# Sheet1.net
KiCad netlist of a schematic drawn in Altium Designer
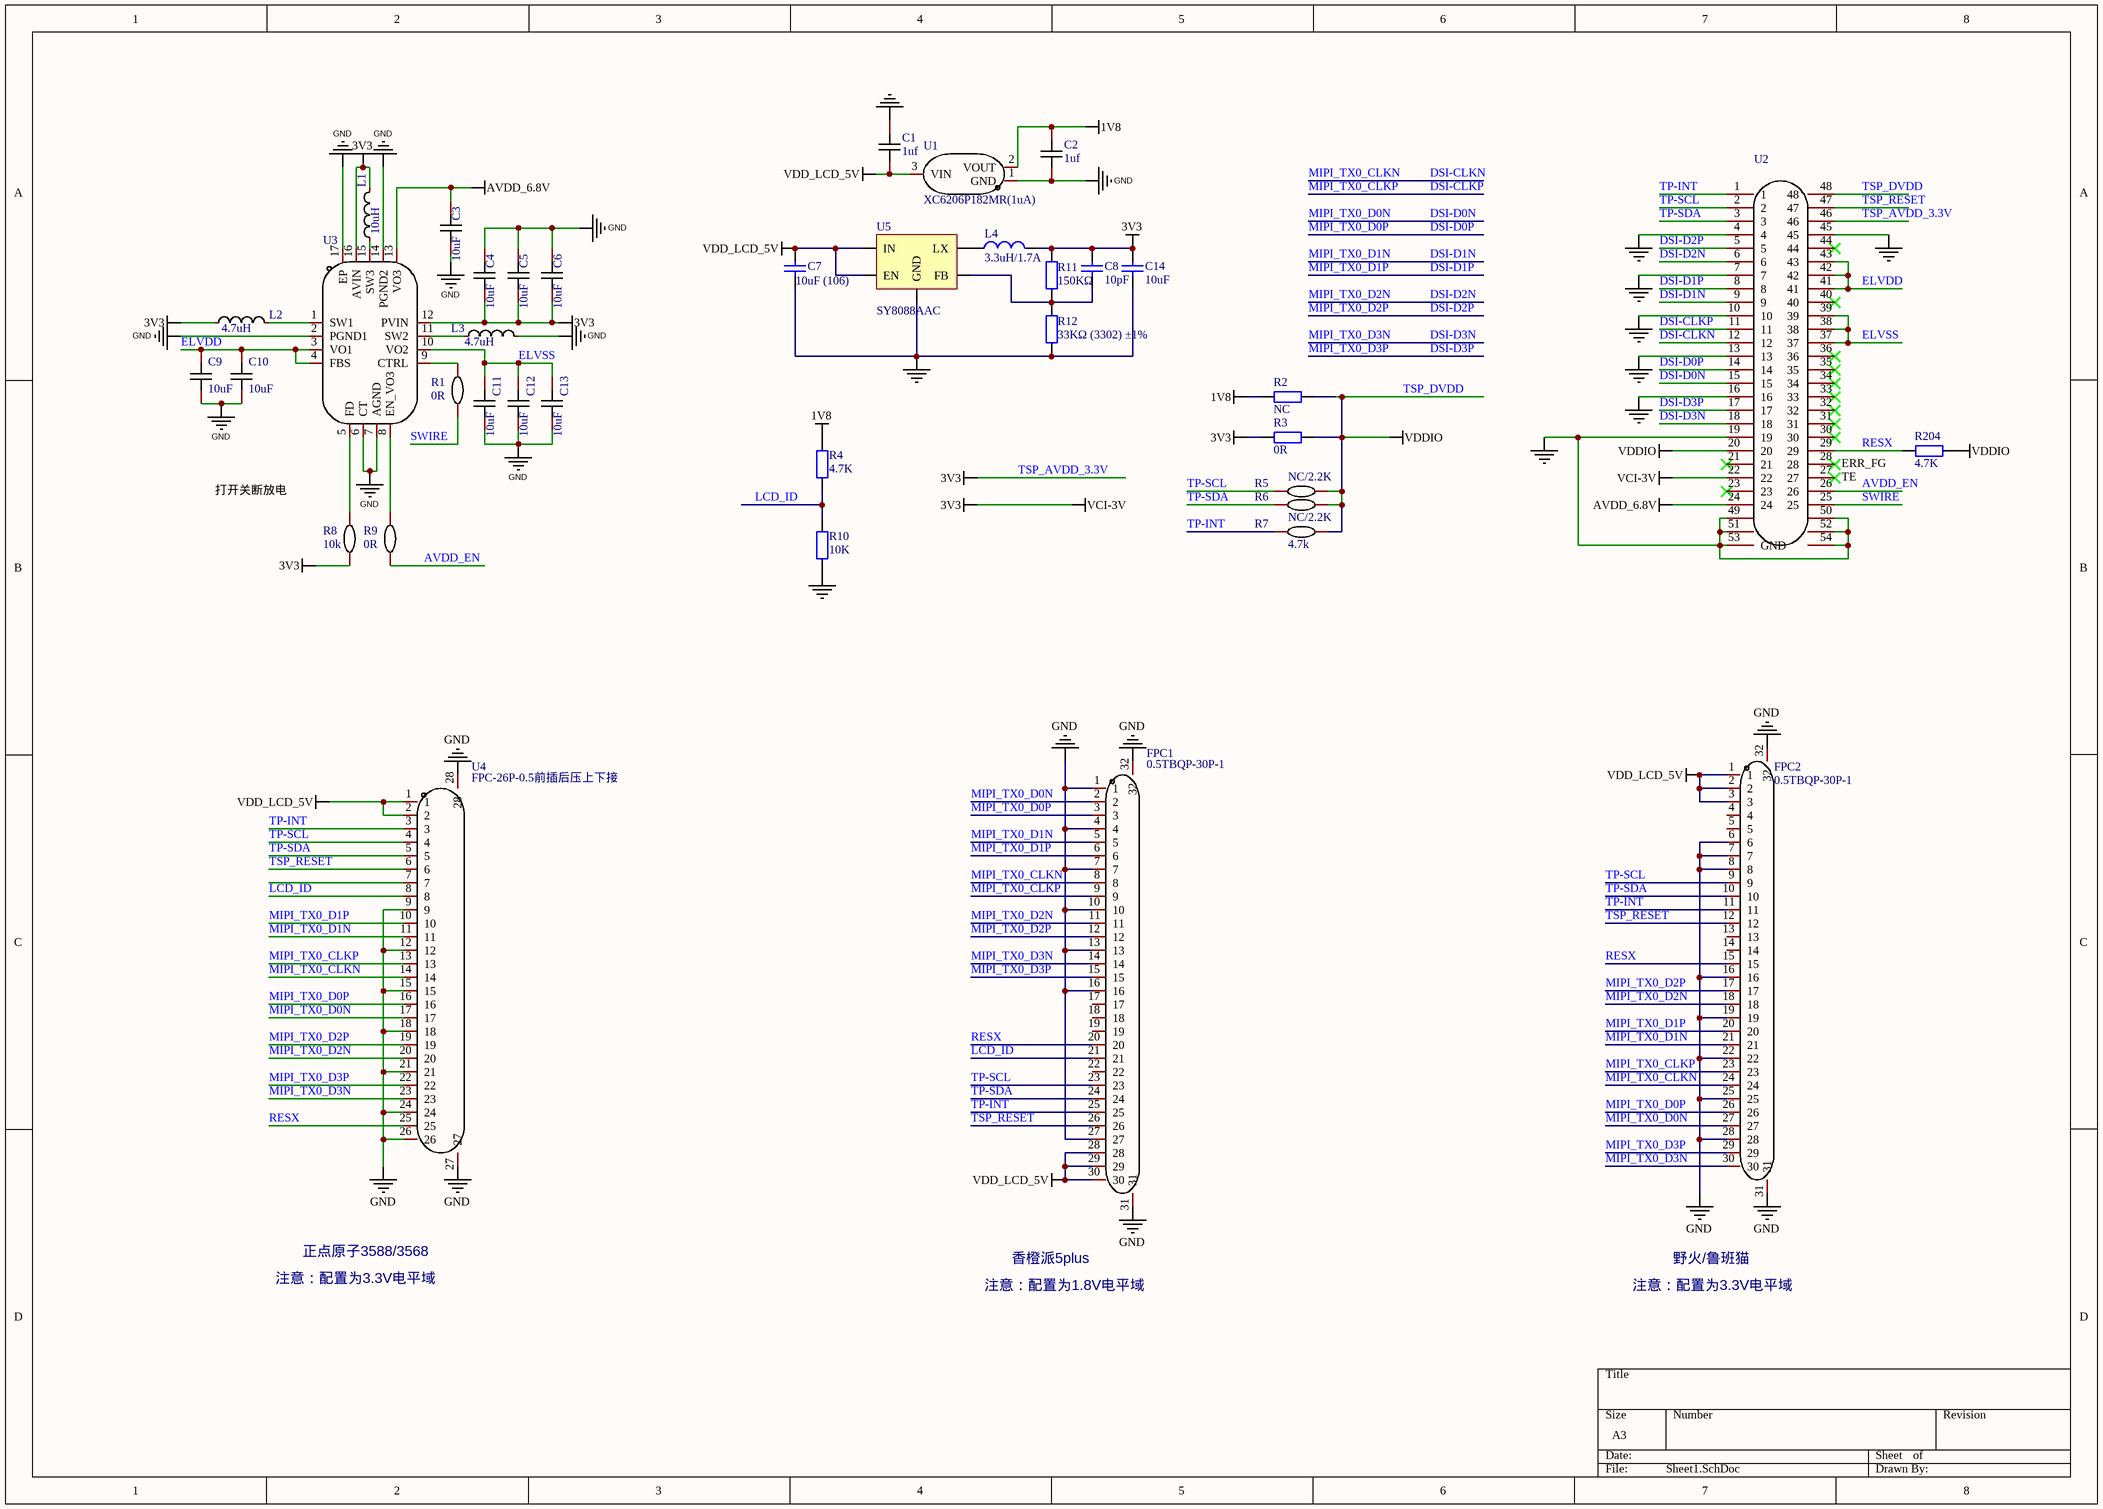
[diagram p0: Sheet1.SchDoc]

(export (version "E")
  (design (tool "Eeschema 10.0.6"))
  (components
    (comp (ref "C1")
      (value "1uf")
      (footprint "C0603")
      (fields (field (name "NAME") "1uf"))
      (libsource (lib "altium-import") (part "root_3_CAP_0603_"))
    )
    (comp (ref "C2")
      (value "1uf")
      (footprint "C0603")
      (fields (field (name "NAME") "1uf"))
      (libsource (lib "altium-import") (part "root_3_CAP_0603_"))
    )
    (comp (ref "C3")
      (value "10uF")
      (footprint "C0603")
      (fields (field (name "NAME") "10uF"))
      (libsource (lib "altium-import") (part "root_1_CAP_0603_"))
    )
    (comp (ref "C4")
      (value "10uF")
      (footprint "C0603")
      (fields (field (name "NAME") "10uF"))
      (libsource (lib "altium-import") (part "root_1_CAP_0603_"))
    )
    (comp (ref "C5")
      (value "10uF")
      (footprint "C0603")
      (fields (field (name "NAME") "10uF"))
      (libsource (lib "altium-import") (part "root_1_CAP_0603_"))
    )
    (comp (ref "C6")
      (value "10uF")
      (footprint "C0603")
      (fields (field (name "NAME") "10uF"))
      (libsource (lib "altium-import") (part "root_1_CAP_0603_"))
    )
    (comp (ref "C7")
      (value "10uF (106)")
      (footprint "C 0603")
      (description "贴片电容")
      (libsource (lib "Miscellaneous Devices LC") (part "0603 10uF (106) 10% 10V"))
    )
    (comp (ref "C8")
      (value "10pF")
      (footprint "C 0603")
      (description "贴片电容")
      (libsource (lib "Miscellaneous Devices LC") (part "0402 10pF (100) 5% 50V"))
    )
    (comp (ref "C9")
      (value "10uF")
      (footprint "C0603")
      (fields (field (name "NAME") "10uF"))
      (libsource (lib "altium-import") (part "root_1_CAP_0603_"))
    )
    (comp (ref "C10")
      (value "10uF")
      (footprint "C0603")
      (fields (field (name "NAME") "10uF"))
      (libsource (lib "altium-import") (part "root_1_CAP_0603_"))
    )
    (comp (ref "C11")
      (value "10uF")
      (footprint "C0603")
      (fields (field (name "NAME") "10uF"))
      (libsource (lib "altium-import") (part "root_1_CAP_0603_"))
    )
    (comp (ref "C12")
      (value "10uF")
      (footprint "C0603")
      (fields (field (name "NAME") "10uF"))
      (libsource (lib "altium-import") (part "root_1_CAP_0603_"))
    )
    (comp (ref "C13")
      (value "10uF")
      (footprint "C0603")
      (fields (field (name "NAME") "10uF"))
      (libsource (lib "altium-import") (part "root_1_CAP_0603_"))
    )
    (comp (ref "C14")
      (value "10uF")
      (footprint "C 0603")
      (description "贴片电容")
      (libsource (lib "Miscellaneous Devices LC") (part "0603 10uF (106) 10% 10V"))
    )
    (comp (ref "FPC1")
      (value "0.5TBQP-30P-1")
      (footprint "FPC-SMD_30P-P0.50_0.5TBQS-30P-1")
      (fields (field (name "NAME") "0.5TBQP-30P-1"))
      (libsource (lib "altium-import") (part "root_0_0.5TBQP-30P-1_"))
    )
    (comp (ref "FPC2")
      (value "0.5TBQP-30P-1")
      (footprint "FPC-SMD_30P-P0.50_0.5TBQS-30P-1")
      (fields (field (name "NAME") "0.5TBQP-30P-1"))
      (libsource (lib "altium-import") (part "root_0_0.5TBQP-30P-1_"))
    )
    (comp (ref "L1")
      (value "10uH")
      (footprint "IND-SMD_L2.7-W2.0")
      (description "电感值:2.2uH;精度:±20%;额定电流:1.3A;")
      (fields
        (field (name "NAME") "10uH")
        (field (name "MANUFACTURER") "gotrend(高创科技)")
        (field (name "MANUFACTURER PART") "GNR2512PA-2R2M")
      )
      (libsource (lib "altium-import") (part "root_1_GNR2512PA-2R2M_"))
    )
    (comp (ref "L2")
      (value "4.7uH")
      (footprint "IND-SMD_L2.7-W2.0")
      (description "电感值:2.2uH;精度:±20%;额定电流:1.3A;")
      (fields
        (field (name "NAME") "4.7uH")
        (field (name "MANUFACTURER") "gotrend(高创科技)")
        (field (name "MANUFACTURER PART") "GNR2512PA-2R2M")
      )
      (libsource (lib "altium-import") (part "root_0_GNR2512PA-2R2M_"))
    )
    (comp (ref "L3")
      (value "4.7uH")
      (footprint "IND-SMD_L2.7-W2.0")
      (description "电感值:2.2uH;精度:±20%;额定电流:1.3A;")
      (fields
        (field (name "NAME") "4.7uH")
        (field (name "MANUFACTURER") "gotrend(高创科技)")
        (field (name "MANUFACTURER PART") "GNR2512PA-2R2M")
      )
      (libsource (lib "altium-import") (part "root_0_GNR2512PA-2R2M_"))
    )
    (comp (ref "L4")
      (value "3.3uH/1.7A")
      (footprint "1008")
      (description "电感")
      (libsource (lib "YZL_Library") (part "Inductor"))
    )
    (comp (ref "R1")
      (value "0R")
      (footprint "R0603")
      (libsource (lib "altium-import") (part "root_1_Res_0603_"))
    )
    (comp (ref "R2")
      (value "NC")
      (footprint "R 0603")
      (description "贴片电阻")
      (fields (field (name "版权归属") "源创客"))
      (libsource (lib "电阻-电容-电感") (part "R"))
    )
    (comp (ref "R3")
      (value "0R")
      (footprint "R 0603")
      (description "贴片电阻")
      (fields (field (name "版权归属") "源创客"))
      (libsource (lib "电阻-电容-电感") (part "R"))
    )
    (comp (ref "R4")
      (value "4.7K")
      (footprint "R 0603")
      (description "贴片电阻")
      (fields (field (name "版权归属") "源创客"))
      (libsource (lib "电阻-电容-电感") (part "R"))
    )
    (comp (ref "R5")
      (value "NC/2.2K")
      (footprint "R0603")
      (libsource (lib "altium-import") (part "root_0_Res_0603_"))
    )
    (comp (ref "R6")
      (value "NC/2.2K")
      (footprint "R0603")
      (libsource (lib "altium-import") (part "root_0_Res_0603_"))
    )
    (comp (ref "R7")
      (value "4.7k")
      (footprint "R0603")
      (libsource (lib "altium-import") (part "root_0_Res_0603_"))
    )
    (comp (ref "R8")
      (value "10k")
      (footprint "R0603")
      (libsource (lib "altium-import") (part "root_1_Res_0603_"))
    )
    (comp (ref "R9")
      (value "0R")
      (footprint "R0603")
      (libsource (lib "altium-import") (part "root_1_Res_0603_"))
    )
    (comp (ref "R10")
      (value "10K")
      (footprint "R 0603")
      (description "贴片电阻")
      (fields (field (name "版权归属") "源创客"))
      (libsource (lib "电阻-电容-电感") (part "R"))
    )
    (comp (ref "R11")
      (value "150KΩ")
      (footprint "R 0603")
      (description "贴片电阻")
      (libsource (lib "Miscellaneous Devices LC") (part "0402 150KΩ (1503) 1%"))
    )
    (comp (ref "R12")
      (value "33KΩ (3302) ±1%")
      (footprint "R 0603")
      (description "贴片电阻")
      (libsource (lib "Miscellaneous Devices LC") (part "0402 33KΩ (3302) 1%"))
    )
    (comp (ref "R204")
      (value "4.7K")
      (footprint "R 0603")
      (description "贴片电阻")
      (fields (field (name "版权归属") "源创客"))
      (libsource (lib "电阻-电容-电感") (part "R"))
    )
    (comp (ref "U1")
      (value "XC6206P182MR(1uA)")
      (footprint "SOT-23-3_L2.9-W1.6-P1.90-LS2.8-BR")
      (description "输出类型:-;")
      (fields (field (name "NAME") "XC6206P182MR(1uA)") (field (name "MANUFACTURER") "TECH PUBLIC(台舟)"))
      (libsource (lib "altium-import") (part "root_2_XC6206P182MR(1uA)_"))
    )
    (comp (ref "U2")
      (value "24-5857-048-201-829+")
      (footprint "BTB-24-5857-048")
      (libsource (lib "altium-import") (part "root_0_24-5857-048-201-829+_"))
    )
    (comp (ref "U3")
      (value "SGM3836AYTQ16G/TR")
      (footprint "TQFN-16_L3.0-W3.0-P0.50-BL-EP1.7")
      (fields (field (name "MANUFACTURER") "SGMICRO(圣邦微)"))
      (libsource (lib "altium-import") (part "root_0_SGM3836AYTQ16G/TR_"))
    )
    (comp (ref "U4")
      (value "FPC-26P-0.5前插后压上下接")
      (footprint "FPC-SMD_26P-P0.50_C9900017209")
      (fields (field (name "NAME") "FPC-26P-0.5前插后压上下接"))
      (libsource (lib "altium-import") (part "root_0_FPC-26P-0.5前插后压上下接_"))
    )
    (comp (ref "U5")
      (value "SY8088AAC")
      (footprint "SOT23-5N")
      (description "1.5M 1A DCDC")
      (libsource (lib "YZL_Library") (part "SY8088AAC"))
    )
  )
  (nets
    (net (code "1") (name "/AVDD_EN") (class "Default")
      (node (ref "R9") (pin "1") (pinfunction "1_1") (pintype "passive"))
      (node (ref "U2") (pin "26") (pinfunction "26_26") (pintype "passive"))
    )
    (net (code "2") (name "/DSI-CLKN") (class "Default")
      (node (ref "FPC1") (pin "8") (pinfunction "8_8") (pintype "passive"))
      (node (ref "FPC2") (pin "24") (pinfunction "24_24") (pintype "passive"))
      (node (ref "U2") (pin "12") (pinfunction "12_12") (pintype "passive"))
      (node (ref "U4") (pin "14") (pinfunction "14_14") (pintype "passive"))
    )
    (net (code "3") (name "/DSI-CLKP") (class "Default")
      (node (ref "FPC1") (pin "9") (pinfunction "9_9") (pintype "passive"))
      (node (ref "FPC2") (pin "23") (pinfunction "23_23") (pintype "passive"))
      (node (ref "U2") (pin "11") (pinfunction "11_11") (pintype "passive"))
      (node (ref "U4") (pin "13") (pinfunction "13_13") (pintype "passive"))
    )
    (net (code "4") (name "/DSI-D0N") (class "Default")
      (node (ref "FPC1") (pin "2") (pinfunction "2_2") (pintype "passive"))
      (node (ref "FPC2") (pin "27") (pinfunction "27_27") (pintype "passive"))
      (node (ref "U2") (pin "15") (pinfunction "15_15") (pintype "passive"))
      (node (ref "U4") (pin "17") (pinfunction "17_17") (pintype "passive"))
    )
    (net (code "5") (name "/DSI-D0P") (class "Default")
      (node (ref "FPC1") (pin "3") (pinfunction "3_3") (pintype "passive"))
      (node (ref "FPC2") (pin "26") (pinfunction "26_26") (pintype "passive"))
      (node (ref "U2") (pin "14") (pinfunction "14_14") (pintype "passive"))
      (node (ref "U4") (pin "16") (pinfunction "16_16") (pintype "passive"))
    )
    (net (code "6") (name "/DSI-D1N") (class "Default")
      (node (ref "FPC1") (pin "5") (pinfunction "5_5") (pintype "passive"))
      (node (ref "FPC2") (pin "21") (pinfunction "21_21") (pintype "passive"))
      (node (ref "U2") (pin "9") (pinfunction "9_9") (pintype "passive"))
      (node (ref "U4") (pin "11") (pinfunction "11_11") (pintype "passive"))
    )
    (net (code "7") (name "/DSI-D1P") (class "Default")
      (node (ref "FPC1") (pin "6") (pinfunction "6_6") (pintype "passive"))
      (node (ref "FPC2") (pin "20") (pinfunction "20_20") (pintype "passive"))
      (node (ref "U2") (pin "8") (pinfunction "8_8") (pintype "passive"))
      (node (ref "U4") (pin "10") (pinfunction "10_10") (pintype "passive"))
    )
    (net (code "8") (name "/DSI-D2N") (class "Default")
      (node (ref "FPC1") (pin "11") (pinfunction "11_11") (pintype "passive"))
      (node (ref "FPC2") (pin "18") (pinfunction "18_18") (pintype "passive"))
      (node (ref "U2") (pin "6") (pinfunction "6_6") (pintype "passive"))
      (node (ref "U4") (pin "20") (pinfunction "20_20") (pintype "passive"))
    )
    (net (code "9") (name "/DSI-D2P") (class "Default")
      (node (ref "FPC1") (pin "12") (pinfunction "12_12") (pintype "passive"))
      (node (ref "FPC2") (pin "17") (pinfunction "17_17") (pintype "passive"))
      (node (ref "U2") (pin "5") (pinfunction "5_5") (pintype "passive"))
      (node (ref "U4") (pin "19") (pinfunction "19_19") (pintype "passive"))
    )
    (net (code "10") (name "/DSI-D3N") (class "Default")
      (node (ref "FPC1") (pin "14") (pinfunction "14_14") (pintype "passive"))
      (node (ref "FPC2") (pin "30") (pinfunction "30_30") (pintype "passive"))
      (node (ref "U2") (pin "18") (pinfunction "18_18") (pintype "passive"))
      (node (ref "U4") (pin "23") (pinfunction "23_23") (pintype "passive"))
    )
    (net (code "11") (name "/DSI-D3P") (class "Default")
      (node (ref "FPC1") (pin "15") (pinfunction "15_15") (pintype "passive"))
      (node (ref "FPC2") (pin "29") (pinfunction "29_29") (pintype "passive"))
      (node (ref "U2") (pin "17") (pinfunction "17_17") (pintype "passive"))
      (node (ref "U4") (pin "22") (pinfunction "22_22") (pintype "passive"))
    )
    (net (code "12") (name "/ELVDD") (class "Default")
      (node (ref "C10") (pin "2") (pinfunction "2_2") (pintype "passive"))
      (node (ref "C9") (pin "2") (pinfunction "2_2") (pintype "passive"))
      (node (ref "U2") (pin "41") (pinfunction "41_41") (pintype "passive"))
      (node (ref "U2") (pin "42") (pinfunction "42_42") (pintype "passive"))
      (node (ref "U2") (pin "43") (pinfunction "43_43") (pintype "passive"))
      (node (ref "U3") (pin "3") (pinfunction "VO1_3") (pintype "passive"))
      (node (ref "U3") (pin "4") (pinfunction "FBS_4") (pintype "passive"))
    )
    (net (code "13") (name "/ELVSS") (class "Default")
      (node (ref "C11") (pin "2") (pinfunction "2_2") (pintype "passive"))
      (node (ref "C12") (pin "2") (pinfunction "2_2") (pintype "passive"))
      (node (ref "C13") (pin "2") (pinfunction "2_2") (pintype "passive"))
      (node (ref "U2") (pin "37") (pinfunction "37_37") (pintype "passive"))
      (node (ref "U2") (pin "38") (pinfunction "38_38") (pintype "passive"))
      (node (ref "U2") (pin "39") (pinfunction "39_39") (pintype "passive"))
      (node (ref "U3") (pin "10") (pinfunction "VO2_10") (pintype "passive"))
    )
    (net (code "14") (name "/LCD_ID") (class "Default")
      (node (ref "FPC1") (pin "21") (pinfunction "21_21") (pintype "passive"))
      (node (ref "R10") (pin "2") (pinfunction "2_2") (pintype "passive"))
      (node (ref "R4") (pin "2") (pinfunction "2_2") (pintype "passive"))
      (node (ref "U4") (pin "8") (pinfunction "8_8") (pintype "passive"))
    )
    (net (code "15") (name "/RESX") (class "Default")
      (node (ref "FPC1") (pin "20") (pinfunction "20_20") (pintype "passive"))
      (node (ref "FPC2") (pin "15") (pinfunction "15_15") (pintype "passive"))
      (node (ref "R204") (pin "1") (pinfunction "1_1") (pintype "passive"))
      (node (ref "U2") (pin "29") (pinfunction "29_29") (pintype "passive"))
      (node (ref "U4") (pin "25") (pinfunction "25_25") (pintype "passive"))
    )
    (net (code "16") (name "/SWIRE") (class "Default")
      (node (ref "R1") (pin "1") (pinfunction "1_1") (pintype "passive"))
      (node (ref "U2") (pin "25") (pinfunction "25_25") (pintype "passive"))
    )
    (net (code "17") (name "/TP-INT") (class "Default")
      (node (ref "FPC1") (pin "25") (pinfunction "25_25") (pintype "passive"))
      (node (ref "FPC2") (pin "11") (pinfunction "11_11") (pintype "passive"))
      (node (ref "R7") (pin "1") (pinfunction "1_1") (pintype "passive"))
      (node (ref "U2") (pin "1") (pinfunction "1_1") (pintype "passive"))
      (node (ref "U4") (pin "3") (pinfunction "3_3") (pintype "passive"))
    )
    (net (code "18") (name "/TP-SCL") (class "Default")
      (node (ref "FPC1") (pin "23") (pinfunction "23_23") (pintype "passive"))
      (node (ref "FPC2") (pin "9") (pinfunction "9_9") (pintype "passive"))
      (node (ref "R5") (pin "1") (pinfunction "1_1") (pintype "passive"))
      (node (ref "U2") (pin "2") (pinfunction "2_2") (pintype "passive"))
      (node (ref "U4") (pin "4") (pinfunction "4_4") (pintype "passive"))
    )
    (net (code "19") (name "/TP-SDA") (class "Default")
      (node (ref "FPC1") (pin "24") (pinfunction "24_24") (pintype "passive"))
      (node (ref "FPC2") (pin "10") (pinfunction "10_10") (pintype "passive"))
      (node (ref "R6") (pin "1") (pinfunction "1_1") (pintype "passive"))
      (node (ref "U2") (pin "3") (pinfunction "3_3") (pintype "passive"))
      (node (ref "U4") (pin "5") (pinfunction "5_5") (pintype "passive"))
    )
    (net (code "20") (name "/TSP_RESET") (class "Default")
      (node (ref "FPC1") (pin "26") (pinfunction "26_26") (pintype "passive"))
      (node (ref "FPC2") (pin "12") (pinfunction "12_12") (pintype "passive"))
      (node (ref "U2") (pin "47") (pinfunction "47_47") (pintype "passive"))
      (node (ref "U4") (pin "6") (pinfunction "6_6") (pintype "passive"))
    )
    (net (code "21") (name "1V8") (class "Default")
      (node (ref "C2") (pin "1") (pinfunction "1_1") (pintype "passive"))
      (node (ref "R2") (pin "1") (pinfunction "1_1") (pintype "passive"))
      (node (ref "R4") (pin "1") (pinfunction "1_1") (pintype "passive"))
      (node (ref "U1") (pin "2") (pinfunction "VOUT_2") (pintype "passive"))
    )
    (net (code "22") (name "3V3") (class "Default")
      (node (ref "C14") (pin "2") (pinfunction "2_2") (pintype "passive"))
      (node (ref "C4") (pin "1") (pinfunction "1_1") (pintype "passive"))
      (node (ref "C5") (pin "1") (pinfunction "1_1") (pintype "passive"))
      (node (ref "C6") (pin "1") (pinfunction "1_1") (pintype "passive"))
      (node (ref "C8") (pin "2") (pinfunction "2_2") (pintype "passive"))
      (node (ref "L1") (pin "2") (pinfunction "2_2") (pintype "passive"))
      (node (ref "L2") (pin "1") (pinfunction "1_1") (pintype "passive"))
      (node (ref "L4") (pin "2") (pinfunction "2_2") (pintype "passive"))
      (node (ref "R11") (pin "2") (pinfunction "2_2") (pintype "passive"))
      (node (ref "R3") (pin "1") (pinfunction "1_1") (pintype "passive"))
      (node (ref "R8") (pin "1") (pinfunction "1_1") (pintype "passive"))
      (node (ref "U2") (pin "22") (pinfunction "22_22") (pintype "passive"))
      (node (ref "U2") (pin "46") (pinfunction "46_46") (pintype "passive"))
      (node (ref "U3") (pin "12") (pinfunction "PVIN_12") (pintype "passive"))
      (node (ref "U3") (pin "16") (pinfunction "AVIN_16") (pintype "passive"))
    )
    (net (code "23") (name "AVDD_6.8V") (class "Default")
      (node (ref "C3") (pin "2") (pinfunction "2_2") (pintype "passive"))
      (node (ref "U2") (pin "24") (pinfunction "24_24") (pintype "passive"))
      (node (ref "U3") (pin "13") (pinfunction "VO3_13") (pintype "passive"))
    )
    (net (code "24") (name "GND") (class "Default")
      (node (ref "C1") (pin "1") (pinfunction "1_1") (pintype "passive"))
      (node (ref "C10") (pin "1") (pinfunction "1_1") (pintype "passive"))
      (node (ref "C11") (pin "1") (pinfunction "1_1") (pintype "passive"))
      (node (ref "C12") (pin "1") (pinfunction "1_1") (pintype "passive"))
      (node (ref "C13") (pin "1") (pinfunction "1_1") (pintype "passive"))
      (node (ref "C14") (pin "1") (pinfunction "1_1") (pintype "passive"))
      (node (ref "C2") (pin "2") (pinfunction "2_2") (pintype "passive"))
      (node (ref "C3") (pin "1") (pinfunction "1_1") (pintype "passive"))
      (node (ref "C4") (pin "2") (pinfunction "2_2") (pintype "passive"))
      (node (ref "C5") (pin "2") (pinfunction "2_2") (pintype "passive"))
      (node (ref "C6") (pin "2") (pinfunction "2_2") (pintype "passive"))
      (node (ref "C7") (pin "1") (pinfunction "1_1") (pintype "passive"))
      (node (ref "C9") (pin "1") (pinfunction "1_1") (pintype "passive"))
      (node (ref "FPC1") (pin "1") (pinfunction "1_1") (pintype "passive"))
      (node (ref "FPC1") (pin "10") (pinfunction "10_10") (pintype "passive"))
      (node (ref "FPC1") (pin "13") (pinfunction "13_13") (pintype "passive"))
      (node (ref "FPC1") (pin "16") (pinfunction "16_16") (pintype "passive"))
      (node (ref "FPC1") (pin "27") (pinfunction "27_27") (pintype "passive"))
      (node (ref "FPC1") (pin "31") (pinfunction "31_31") (pintype "passive"))
      (node (ref "FPC1") (pin "32") (pinfunction "32_32") (pintype "passive"))
      (node (ref "FPC1") (pin "4") (pinfunction "4_4") (pintype "passive"))
      (node (ref "FPC1") (pin "7") (pinfunction "7_7") (pintype "passive"))
      (node (ref "FPC2") (pin "16") (pinfunction "16_16") (pintype "passive"))
      (node (ref "FPC2") (pin "19") (pinfunction "19_19") (pintype "passive"))
      (node (ref "FPC2") (pin "22") (pinfunction "22_22") (pintype "passive"))
      (node (ref "FPC2") (pin "25") (pinfunction "25_25") (pintype "passive"))
      (node (ref "FPC2") (pin "28") (pinfunction "28_28") (pintype "passive"))
      (node (ref "FPC2") (pin "31") (pinfunction "31_31") (pintype "passive"))
      (node (ref "FPC2") (pin "32") (pinfunction "32_32") (pintype "passive"))
      (node (ref "FPC2") (pin "6") (pinfunction "6_6") (pintype "passive"))
      (node (ref "FPC2") (pin "7") (pinfunction "7_7") (pintype "passive"))
      (node (ref "FPC2") (pin "8") (pinfunction "8_8") (pintype "passive"))
      (node (ref "L3") (pin "2") (pinfunction "2_2") (pintype "passive"))
      (node (ref "R10") (pin "1") (pinfunction "1_1") (pintype "passive"))
      (node (ref "R12") (pin "1") (pinfunction "1_1") (pintype "passive"))
      (node (ref "U1") (pin "1") (pinfunction "GND_1") (pintype "passive"))
      (node (ref "U2") (pin "10") (pinfunction "10_10") (pintype "passive"))
      (node (ref "U2") (pin "13") (pinfunction "13_13") (pintype "passive"))
      (node (ref "U2") (pin "16") (pinfunction "16_16") (pintype "passive"))
      (node (ref "U2") (pin "19") (pinfunction "19_19") (pintype "passive"))
      (node (ref "U2") (pin "4") (pinfunction "4_4") (pintype "passive"))
      (node (ref "U2") (pin "45") (pinfunction "45_45") (pintype "passive"))
      (node (ref "U2") (pin "49") (pinfunction "48_49") (pintype "passive"))
      (node (ref "U2") (pin "50") (pinfunction "48_50") (pintype "passive"))
      (node (ref "U2") (pin "51") (pinfunction "48_51") (pintype "passive"))
      (node (ref "U2") (pin "52") (pinfunction "48_52") (pintype "passive"))
      (node (ref "U2") (pin "53") (pinfunction "GND_53") (pintype "passive"))
      (node (ref "U2") (pin "54") (pinfunction "48_54") (pintype "passive"))
      (node (ref "U2") (pin "7") (pinfunction "7_7") (pintype "passive"))
      (node (ref "U3") (pin "14") (pinfunction "PGND2_14") (pintype "passive"))
      (node (ref "U3") (pin "17") (pinfunction "EP_17") (pintype "passive"))
      (node (ref "U3") (pin "2") (pinfunction "PGND1_2") (pintype "passive"))
      (node (ref "U3") (pin "6") (pinfunction "CT_6") (pintype "passive"))
      (node (ref "U3") (pin "7") (pinfunction "AGND_7") (pintype "passive"))
      (node (ref "U4") (pin "12") (pinfunction "12_12") (pintype "passive"))
      (node (ref "U4") (pin "15") (pinfunction "15_15") (pintype "passive"))
      (node (ref "U4") (pin "18") (pinfunction "18_18") (pintype "passive"))
      (node (ref "U4") (pin "21") (pinfunction "21_21") (pintype "passive"))
      (node (ref "U4") (pin "24") (pinfunction "24_24") (pintype "passive"))
      (node (ref "U4") (pin "26") (pinfunction "26_26") (pintype "passive"))
      (node (ref "U4") (pin "27") (pinfunction "27_27") (pintype "passive"))
      (node (ref "U4") (pin "28") (pinfunction "28_28") (pintype "passive"))
      (node (ref "U4") (pin "9") (pinfunction "9_9") (pintype "passive"))
      (node (ref "U5") (pin "2") (pinfunction "GND_2") (pintype "passive"))
    )
    (net (code "25") (name "Net-(U3-CTRL)") (class "Default")
      (node (ref "R1") (pin "2") (pinfunction "2_2") (pintype "passive"))
      (node (ref "U3") (pin "9") (pinfunction "CTRL_9") (pintype "passive"))
    )
    (net (code "26") (name "Net-(U3-EN_VO3)") (class "Default")
      (node (ref "R9") (pin "2") (pinfunction "2_2") (pintype "passive"))
      (node (ref "U3") (pin "8") (pinfunction "EN_VO3_8") (pintype "passive"))
    )
    (net (code "27") (name "Net-(U3-FD)") (class "Default")
      (node (ref "R8") (pin "2") (pinfunction "2_2") (pintype "passive"))
      (node (ref "U3") (pin "5") (pinfunction "FD_5") (pintype "passive"))
    )
    (net (code "28") (name "Net-(U3-SW1)") (class "Default")
      (node (ref "L2") (pin "2") (pinfunction "2_2") (pintype "passive"))
      (node (ref "U3") (pin "1") (pinfunction "SW1_1") (pintype "passive"))
    )
    (net (code "29") (name "Net-(U3-SW2)") (class "Default")
      (node (ref "L3") (pin "1") (pinfunction "1_1") (pintype "passive"))
      (node (ref "U3") (pin "11") (pinfunction "SW2_11") (pintype "passive"))
    )
    (net (code "30") (name "Net-(U3-SW3)") (class "Default")
      (node (ref "L1") (pin "1") (pinfunction "1_1") (pintype "passive"))
      (node (ref "U3") (pin "15") (pinfunction "SW3_15") (pintype "passive"))
    )
    (net (code "31") (name "Net-(U5-FB)") (class "Default")
      (node (ref "C8") (pin "1") (pinfunction "1_1") (pintype "passive"))
      (node (ref "R11") (pin "1") (pinfunction "1_1") (pintype "passive"))
      (node (ref "R12") (pin "2") (pinfunction "2_2") (pintype "passive"))
      (node (ref "U5") (pin "5") (pinfunction "FB_5") (pintype "passive"))
    )
    (net (code "32") (name "Net-(U5-LX)") (class "Default")
      (node (ref "L4") (pin "1") (pinfunction "1_1") (pintype "passive"))
      (node (ref "U5") (pin "3") (pinfunction "LX_3") (pintype "passive"))
    )
    (net (code "33") (name "VDDIO") (class "Default")
      (node (ref "R2") (pin "2") (pinfunction "2_2") (pintype "passive"))
      (node (ref "R204") (pin "2") (pinfunction "2_2") (pintype "passive"))
      (node (ref "R3") (pin "2") (pinfunction "2_2") (pintype "passive"))
      (node (ref "R5") (pin "2") (pinfunction "2_2") (pintype "passive"))
      (node (ref "R6") (pin "2") (pinfunction "2_2") (pintype "passive"))
      (node (ref "R7") (pin "2") (pinfunction "2_2") (pintype "passive"))
      (node (ref "U2") (pin "20") (pinfunction "20_20") (pintype "passive"))
      (node (ref "U2") (pin "48") (pinfunction "48_48") (pintype "passive"))
    )
    (net (code "34") (name "VDD_LCD_5V") (class "Default")
      (node (ref "C1") (pin "2") (pinfunction "2_2") (pintype "passive"))
      (node (ref "C7") (pin "2") (pinfunction "2_2") (pintype "passive"))
      (node (ref "FPC1") (pin "28") (pinfunction "28_28") (pintype "passive"))
      (node (ref "FPC1") (pin "29") (pinfunction "29_29") (pintype "passive"))
      (node (ref "FPC1") (pin "30") (pinfunction "30_30") (pintype "passive"))
      (node (ref "FPC2") (pin "1") (pinfunction "1_1") (pintype "passive"))
      (node (ref "FPC2") (pin "2") (pinfunction "2_2") (pintype "passive"))
      (node (ref "FPC2") (pin "3") (pinfunction "3_3") (pintype "passive"))
      (node (ref "U1") (pin "3") (pinfunction "VIN_3") (pintype "passive"))
      (node (ref "U4") (pin "1") (pinfunction "1_1") (pintype "passive"))
      (node (ref "U4") (pin "2") (pinfunction "2_2") (pintype "passive"))
      (node (ref "U5") (pin "1") (pinfunction "EN_1") (pintype "passive"))
      (node (ref "U5") (pin "4") (pinfunction "IN_4") (pintype "passive"))
    )
    (net (code "35") (name "unconnected-(FPC1-Pad17)") (class "Default")
      (node (ref "FPC1") (pin "17") (pinfunction "17_17") (pintype "passive"))
    )
    (net (code "36") (name "unconnected-(FPC1-Pad18)") (class "Default")
      (node (ref "FPC1") (pin "18") (pinfunction "18_18") (pintype "passive"))
    )
    (net (code "37") (name "unconnected-(FPC1-Pad19)") (class "Default")
      (node (ref "FPC1") (pin "19") (pinfunction "19_19") (pintype "passive"))
    )
    (net (code "38") (name "unconnected-(FPC1-Pad22)") (class "Default")
      (node (ref "FPC1") (pin "22") (pinfunction "22_22") (pintype "passive"))
    )
    (net (code "39") (name "unconnected-(FPC2-Pad4)") (class "Default")
      (node (ref "FPC2") (pin "4") (pinfunction "4_4") (pintype "passive"))
    )
    (net (code "40") (name "unconnected-(FPC2-Pad5)") (class "Default")
      (node (ref "FPC2") (pin "5") (pinfunction "5_5") (pintype "passive"))
    )
    (net (code "41") (name "unconnected-(FPC2-Pad13)") (class "Default")
      (node (ref "FPC2") (pin "13") (pinfunction "13_13") (pintype "passive"))
    )
    (net (code "42") (name "unconnected-(FPC2-Pad14)") (class "Default")
      (node (ref "FPC2") (pin "14") (pinfunction "14_14") (pintype "passive"))
    )
    (net (code "43") (name "unconnected-(U2-Pad21)") (class "Default")
      (node (ref "U2") (pin "21") (pinfunction "21_21") (pintype "passive+no_connect"))
    )
    (net (code "44") (name "unconnected-(U2-Pad23)") (class "Default")
      (node (ref "U2") (pin "23") (pinfunction "23_23") (pintype "passive+no_connect"))
    )
    (net (code "45") (name "unconnected-(U2-Pad27)") (class "Default")
      (node (ref "U2") (pin "27") (pinfunction "27_27") (pintype "passive+no_connect"))
    )
    (net (code "46") (name "unconnected-(U2-Pad28)") (class "Default")
      (node (ref "U2") (pin "28") (pinfunction "28_28") (pintype "passive+no_connect"))
    )
    (net (code "47") (name "unconnected-(U2-Pad30)") (class "Default")
      (node (ref "U2") (pin "30") (pinfunction "30_30") (pintype "passive+no_connect"))
    )
    (net (code "48") (name "unconnected-(U2-Pad31)") (class "Default")
      (node (ref "U2") (pin "31") (pinfunction "31_31") (pintype "passive+no_connect"))
    )
    (net (code "49") (name "unconnected-(U2-Pad32)") (class "Default")
      (node (ref "U2") (pin "32") (pinfunction "32_32") (pintype "passive+no_connect"))
    )
    (net (code "50") (name "unconnected-(U2-Pad33)") (class "Default")
      (node (ref "U2") (pin "33") (pinfunction "33_33") (pintype "passive+no_connect"))
    )
    (net (code "51") (name "unconnected-(U2-Pad34)") (class "Default")
      (node (ref "U2") (pin "34") (pinfunction "34_34") (pintype "passive+no_connect"))
    )
    (net (code "52") (name "unconnected-(U2-Pad35)") (class "Default")
      (node (ref "U2") (pin "35") (pinfunction "35_35") (pintype "passive+no_connect"))
    )
    (net (code "53") (name "unconnected-(U2-Pad36)") (class "Default")
      (node (ref "U2") (pin "36") (pinfunction "36_36") (pintype "passive+no_connect"))
    )
    (net (code "54") (name "unconnected-(U2-Pad40)") (class "Default")
      (node (ref "U2") (pin "40") (pinfunction "40_40") (pintype "passive+no_connect"))
    )
    (net (code "55") (name "unconnected-(U2-Pad44)") (class "Default")
      (node (ref "U2") (pin "44") (pinfunction "44_44") (pintype "passive+no_connect"))
    )
    (net (code "56") (name "unconnected-(U4-Pad7)") (class "Default")
      (node (ref "U4") (pin "7") (pinfunction "7_7") (pintype "passive"))
    )
  )
)
